# Interface_Protection.net
KiCad netlist of a schematic drawn in Altium Designer
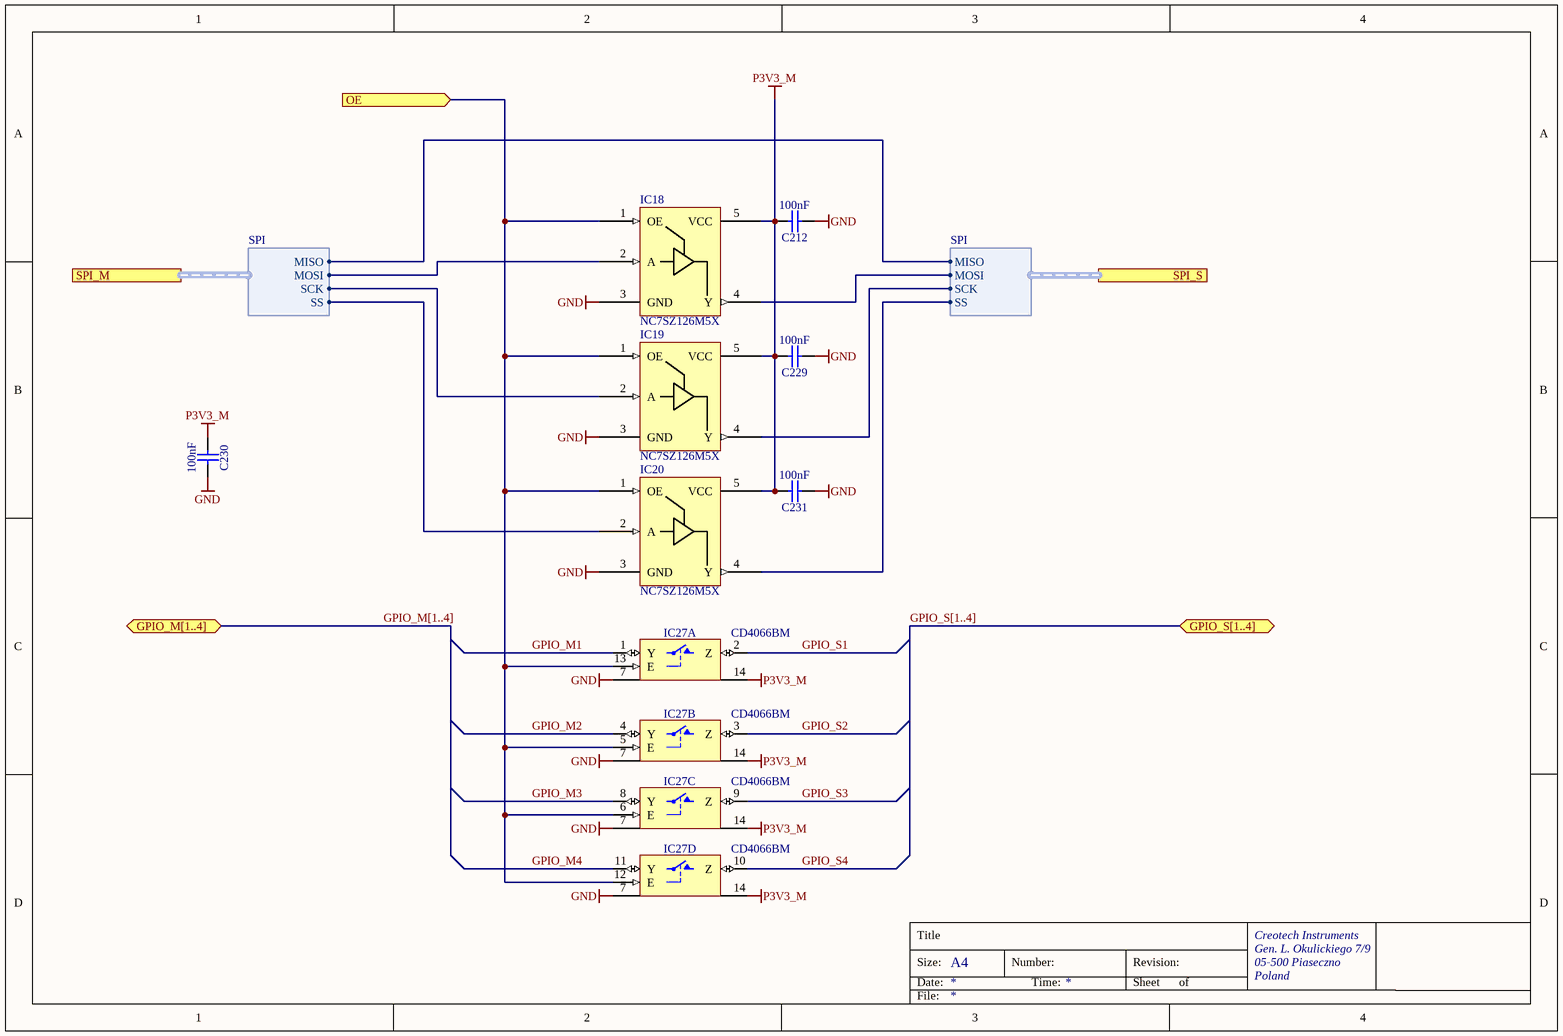
[diagram p0: Interface_Protection.SchDoc]

(export (version "E")
  (design (tool "Eeschema 10.0.6"))
  (components
    (comp (ref "C212")
      (value "100nF")
      (footprint "CAPC1608X87N")
      (description "Non-polarised capacitor")
      (fields
        (field (name "PART NUMBER") "CC0603_100NF_50V_10%_X7R")
        (field (name "VOLTAGE") "50V")
        (field (name "AUTHOR") "CERN DEM JLC")
      )
      (libsource (lib "Capacitors") (part "Capacitor - non polarized"))
    )
    (comp (ref "C229")
      (value "100nF")
      (footprint "CAPC1608X87N")
      (description "Non-polarised capacitor")
      (fields
        (field (name "PART NUMBER") "CC0603_100NF_50V_10%_X7R")
        (field (name "VOLTAGE") "50V")
        (field (name "AUTHOR") "CERN DEM JLC")
      )
      (libsource (lib "Capacitors") (part "Capacitor - non polarized"))
    )
    (comp (ref "C230")
      (value "100nF")
      (footprint "CAPC1608X87N")
      (description "Non-polarised capacitor")
      (fields
        (field (name "PART NUMBER") "CC0603_100NF_50V_10%_X7R")
        (field (name "VOLTAGE") "50V")
        (field (name "AUTHOR") "CERN DEM JLC")
      )
      (libsource (lib "Capacitors") (part "Capacitor - non polarized"))
    )
    (comp (ref "C231")
      (value "100nF")
      (footprint "CAPC1608X87N")
      (description "Non-polarised capacitor")
      (fields
        (field (name "PART NUMBER") "CC0603_100NF_50V_10%_X7R")
        (field (name "VOLTAGE") "50V")
        (field (name "AUTHOR") "CERN DEM JLC")
      )
      (libsource (lib "Capacitors") (part "Capacitor - non polarized"))
    )
    (comp (ref "IC18")
      (value "NC7SZ126M5X")
      (footprint "SOT95P280X145-5N")
      (libsource (lib "LIBRARY_SCH") (part "74_NC7SZ126M5X"))
    )
    (comp (ref "IC19")
      (value "NC7SZ126M5X")
      (footprint "SOT95P280X145-5N")
      (libsource (lib "LIBRARY_SCH") (part "74_NC7SZ126M5X"))
    )
    (comp (ref "IC20")
      (value "NC7SZ126M5X")
      (footprint "SOT95P280X145-5N")
      (libsource (lib "LIBRARY_SCH") (part "74_NC7SZ126M5X"))
    )
    (comp (ref "IC27")
      (value "CD4066BM")
      (footprint "SOIC127P600X175-14N")
      (fields (field (name "MANUFACTURER") "TEXAS INSTRUMENTS") (field (name "AUTHOR") "CERN DEM MR"))
      (libsource (lib "ICs And Semiconductors") (part "4066_a"))
    )
  )
  (nets
    (net (code "2") (name "/GPIO_M1") (class "Default")
      (node (ref "IC27") (pin "1") (pinfunction "Y_1") (pintype "bidirectional"))
    )
    (net (code "3") (name "/GPIO_M2") (class "Default")
      (node (ref "IC27") (pin "4") (pinfunction "Y_4") (pintype "bidirectional"))
    )
    (net (code "4") (name "/GPIO_M3") (class "Default")
      (node (ref "IC27") (pin "8") (pinfunction "Y_8") (pintype "bidirectional"))
    )
    (net (code "5") (name "/GPIO_M4") (class "Default")
      (node (ref "IC27") (pin "11") (pinfunction "Y_11") (pintype "bidirectional"))
    )
    (net (code "7") (name "/GPIO_S1") (class "Default")
      (node (ref "IC27") (pin "2") (pinfunction "Z_2") (pintype "bidirectional"))
    )
    (net (code "8") (name "/GPIO_S2") (class "Default")
      (node (ref "IC27") (pin "3") (pinfunction "Z_3") (pintype "bidirectional"))
    )
    (net (code "9") (name "/GPIO_S3") (class "Default")
      (node (ref "IC27") (pin "9") (pinfunction "Z_9") (pintype "bidirectional"))
    )
    (net (code "10") (name "/GPIO_S4") (class "Default")
      (node (ref "IC27") (pin "10") (pinfunction "Z_10") (pintype "bidirectional"))
    )
    (net (code "12") (name "/OE") (class "Default")
      (node (ref "IC18") (pin "1") (pinfunction "OE_1") (pintype "input"))
      (node (ref "IC19") (pin "1") (pinfunction "OE_1") (pintype "input"))
      (node (ref "IC20") (pin "1") (pinfunction "OE_1") (pintype "input"))
      (node (ref "IC27") (pin "12") (pinfunction "E_12") (pintype "input"))
      (node (ref "IC27") (pin "13") (pinfunction "E_13") (pintype "input"))
      (node (ref "IC27") (pin "5") (pinfunction "E_5") (pintype "input"))
      (node (ref "IC27") (pin "6") (pinfunction "E_6") (pintype "input"))
    )
    (net (code "14") (name "GND") (class "Default")
      (node (ref "C212") (pin "1") (pinfunction "1_1") (pintype "passive"))
      (node (ref "C229") (pin "1") (pinfunction "1_1") (pintype "passive"))
      (node (ref "C230") (pin "2") (pinfunction "2_2") (pintype "passive"))
      (node (ref "C231") (pin "1") (pinfunction "1_1") (pintype "passive"))
      (node (ref "IC18") (pin "3") (pinfunction "GND_3") (pintype "power_in"))
      (node (ref "IC19") (pin "3") (pinfunction "GND_3") (pintype "power_in"))
      (node (ref "IC20") (pin "3") (pinfunction "GND_3") (pintype "power_in"))
      (node (ref "IC27") (pin "7") (pinfunction "VSS_7") (pintype "power_in"))
    )
    (net (code "15") (name "P3V3_M") (class "Default")
      (node (ref "C212") (pin "2") (pinfunction "2_2") (pintype "passive"))
      (node (ref "C229") (pin "2") (pinfunction "2_2") (pintype "passive"))
      (node (ref "C230") (pin "1") (pinfunction "1_1") (pintype "passive"))
      (node (ref "C231") (pin "2") (pinfunction "2_2") (pintype "passive"))
      (node (ref "IC18") (pin "5") (pinfunction "VCC_5") (pintype "power_in"))
      (node (ref "IC19") (pin "5") (pinfunction "VCC_5") (pintype "power_in"))
      (node (ref "IC20") (pin "5") (pinfunction "VCC_5") (pintype "power_in"))
      (node (ref "IC27") (pin "14") (pinfunction "VDD_14") (pintype "power_in"))
    )
    (net (code "16") (name "unconnected-(IC18-A-Pad2)") (class "Default")
      (node (ref "IC18") (pin "2") (pinfunction "A_2") (pintype "input"))
    )
    (net (code "17") (name "unconnected-(IC18-Y-Pad4)") (class "Default")
      (node (ref "IC18") (pin "4") (pinfunction "Y_4") (pintype "output"))
    )
    (net (code "18") (name "unconnected-(IC19-A-Pad2)") (class "Default")
      (node (ref "IC19") (pin "2") (pinfunction "A_2") (pintype "input"))
    )
    (net (code "19") (name "unconnected-(IC19-Y-Pad4)") (class "Default")
      (node (ref "IC19") (pin "4") (pinfunction "Y_4") (pintype "output"))
    )
    (net (code "20") (name "unconnected-(IC20-A-Pad2)") (class "Default")
      (node (ref "IC20") (pin "2") (pinfunction "A_2") (pintype "input"))
    )
    (net (code "21") (name "unconnected-(IC20-Y-Pad4)") (class "Default")
      (node (ref "IC20") (pin "4") (pinfunction "Y_4") (pintype "output"))
    )
  )
)
